# OPA567.net
KiCad netlist of a schematic drawn in Altium Designer
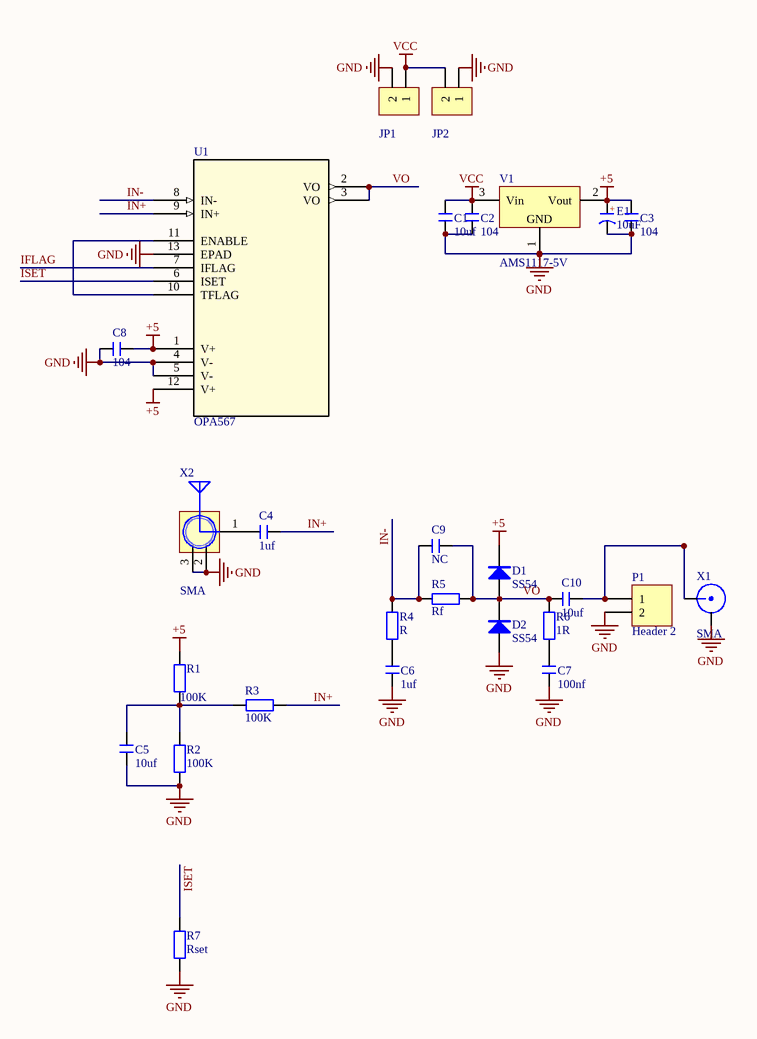
[diagram p0: OPA567.SchDoc]

(export (version "E")
  (design (tool "Eeschema 10.0.6"))
  (components
    (comp (ref "C1")
      (value "10uf")
      (footprint "C 0603_L")
      (description "无极性贴片电容")
      (fields (field (name "版权归属") "源创客"))
      (libsource (lib "IL") (part "C"))
    )
    (comp (ref "C2")
      (value "104")
      (footprint "C 0603_L")
      (description "无极性贴片电容")
      (fields (field (name "版权归属") "源创客"))
      (libsource (lib "IL") (part "C"))
    )
    (comp (ref "C3")
      (value "104")
      (footprint "C 0603_L")
      (description "无极性贴片电容")
      (fields (field (name "版权归属") "源创客"))
      (libsource (lib "IL") (part "C"))
    )
    (comp (ref "C4")
      (value "1uf")
      (footprint "C 0603_L")
      (description "无极性贴片电容")
      (fields (field (name "版权归属") "源创客"))
      (libsource (lib "IL") (part "C"))
    )
    (comp (ref "C5")
      (value "10uf")
      (footprint "C 0603_L")
      (description "无极性贴片电容")
      (fields (field (name "版权归属") "源创客"))
      (libsource (lib "IL") (part "C"))
    )
    (comp (ref "C6")
      (value "1uf")
      (footprint "C 0603_L")
      (description "无极性贴片电容")
      (fields (field (name "版权归属") "源创客"))
      (libsource (lib "IL") (part "C"))
    )
    (comp (ref "C7")
      (value "100nf")
      (footprint "C 0603_L")
      (description "无极性贴片电容")
      (fields (field (name "版权归属") "源创客"))
      (libsource (lib "IL") (part "C"))
    )
    (comp (ref "C8")
      (value "104")
      (footprint "C 0603_L")
      (description "无极性贴片电容")
      (fields (field (name "版权归属") "源创客"))
      (libsource (lib "IL") (part "C"))
    )
    (comp (ref "C9")
      (value "NC")
      (footprint "C 0603_L")
      (description "无极性贴片电容")
      (fields (field (name "版权归属") "源创客"))
      (libsource (lib "IL") (part "C"))
    )
    (comp (ref "C10")
      (value "10uf")
      (footprint "C 0603_L")
      (description "无极性贴片电容")
      (fields (field (name "版权归属") "源创客"))
      (libsource (lib "IL") (part "C"))
    )
    (comp (ref "D1")
      (value "SS54")
      (footprint "SMA")
      (description "肖特基二极管")
      (fields (field (name "版权归属") "源创客"))
      (libsource (lib "IL") (part "SR540"))
    )
    (comp (ref "D2")
      (value "SS54")
      (footprint "SMA")
      (description "肖特基二极管")
      (fields (field (name "版权归属") "源创客"))
      (libsource (lib "IL") (part "SR540"))
    )
    (comp (ref "E1")
      (value "10uF")
      (footprint "CD B(3528)")
      (description "贴片钽电容")
      (fields (field (name "版权归属") "源创客"))
      (libsource (lib "IL") (part "C-CD"))
    )
    (comp (ref "JP1")
      (value "HDR-1X2")
      (footprint "VH3.96-LI-2P")
      (description "2P接插件")
      (fields (field (name "版权归属") "源创客"))
      (libsource (lib "IL") (part "Header 2_1"))
    )
    (comp (ref "JP2")
      (value "HDR-1X2")
      (footprint "VH3.96-LI-2P")
      (description "2P接插件")
      (fields (field (name "版权归属") "源创客"))
      (libsource (lib "IL") (part "Header 2_1"))
    )
    (comp (ref "P1")
      (value "Header 2")
      (footprint "HDR1X2")
      (description "Header, 2-Pin")
      (fields (field (name "PUBLISHER") "Altium Limited"))
      (libsource (lib "Miscellaneous Connectors") (part "Header 2"))
    )
    (comp (ref "R1")
      (value "100K")
      (footprint "R 0603_L")
      (description "贴片电阻")
      (fields (field (name "版权归属") "源创客"))
      (libsource (lib "IL") (part "R"))
    )
    (comp (ref "R2")
      (value "100K")
      (footprint "R 0603_L")
      (description "贴片电阻")
      (fields (field (name "版权归属") "源创客"))
      (libsource (lib "IL") (part "R"))
    )
    (comp (ref "R3")
      (value "100K")
      (footprint "R 0603_L")
      (description "贴片电阻")
      (fields (field (name "版权归属") "源创客"))
      (libsource (lib "IL") (part "R"))
    )
    (comp (ref "R4")
      (value "R")
      (footprint "R 0603_L")
      (description "贴片电阻")
      (fields (field (name "版权归属") "源创客"))
      (libsource (lib "IL") (part "R"))
    )
    (comp (ref "R5")
      (value "Rf")
      (footprint "R 0603_L")
      (description "贴片电阻")
      (fields (field (name "版权归属") "源创客"))
      (libsource (lib "IL") (part "R"))
    )
    (comp (ref "R6")
      (value "1R")
      (footprint "R 0603_L")
      (description "贴片电阻")
      (fields (field (name "版权归属") "源创客"))
      (libsource (lib "IL") (part "R"))
    )
    (comp (ref "R7")
      (value "Rset")
      (footprint "R 0603_L")
      (description "贴片电阻")
      (fields (field (name "版权归属") "源创客"))
      (libsource (lib "IL") (part "R"))
    )
    (comp (ref "U1")
      (value "OPA567")
      (footprint "RHG12_3P12X3P12")
      (description "2A,5V功率放大器")
      (fields
        (field (name "MANUFACTURER_PART_NUMBER") "OPA567AIRHGR")
        (field (name "COPYRIGHT") "Copyright (C) 2021 Ultra Librarian. All rights reserved.")
      )
      (libsource (lib "IL") (part "OPA567AIRHGR"))
    )
    (comp (ref "V1")
      (value "AMS1117-5V")
      (footprint "SOT223_L")
      (description "三端稳压芯片")
      (fields (field (name "版权归属") "源创客"))
      (libsource (lib "IL") (part "AMS1117"))
    )
    (comp (ref "X1") (value "SMA") (footprint "SMA1") (libsource (lib "Library") (part "SMA")))
    (comp (ref "X2")
      (value "SMA")
      (footprint "SMA-KE")
      (description "SMA-2.4G射频天线接口")
      (fields (field (name "版权归属") "源创客"))
      (libsource (lib "IL") (part "SMA"))
    )
  )
  (nets
    (net (code "1") (name "+5") (class "Default")
      (node (ref "C3") (pin "2") (pinfunction "2_2") (pintype "passive"))
      (node (ref "C8") (pin "1") (pinfunction "1_1") (pintype "passive"))
      (node (ref "D1") (pin "2") (pinfunction "K_2") (pintype "passive"))
      (node (ref "E1") (pin "1") (pinfunction "A_1") (pintype "passive"))
      (node (ref "R1") (pin "2") (pinfunction "2_2") (pintype "passive"))
      (node (ref "U1") (pin "1") (pinfunction "V+_1") (pintype "power_in"))
      (node (ref "U1") (pin "12") (pinfunction "V+_12") (pintype "power_in"))
      (node (ref "V1") (pin "2") (pinfunction "Vout_2") (pintype "passive"))
    )
    (net (code "2") (name "/IFLAG") (class "Default")
      (node (ref "U1") (pin "7") (pinfunction "IFLAG_7") (pintype "passive"))
    )
    (net (code "3") (name "/IN+") (class "Default")
      (node (ref "C4") (pin "1") (pinfunction "1_1") (pintype "passive"))
      (node (ref "R3") (pin "2") (pinfunction "2_2") (pintype "passive"))
      (node (ref "U1") (pin "9") (pinfunction "IN+_9") (pintype "input"))
    )
    (net (code "4") (name "/IN-") (class "Default")
      (node (ref "C9") (pin "2") (pinfunction "2_2") (pintype "passive"))
      (node (ref "R4") (pin "2") (pinfunction "2_2") (pintype "passive"))
      (node (ref "R5") (pin "2") (pinfunction "2_2") (pintype "passive"))
      (node (ref "U1") (pin "8") (pinfunction "IN-_8") (pintype "input"))
    )
    (net (code "5") (name "/ISET") (class "Default")
      (node (ref "R7") (pin "1") (pinfunction "1_1") (pintype "passive"))
      (node (ref "U1") (pin "6") (pinfunction "ISET_6") (pintype "passive"))
    )
    (net (code "6") (name "/VO") (class "Default")
      (node (ref "C10") (pin "2") (pinfunction "2_2") (pintype "passive"))
      (node (ref "C9") (pin "1") (pinfunction "1_1") (pintype "passive"))
      (node (ref "D1") (pin "1") (pinfunction "A_1") (pintype "passive"))
      (node (ref "D2") (pin "2") (pinfunction "K_2") (pintype "passive"))
      (node (ref "R5") (pin "1") (pinfunction "1_1") (pintype "passive"))
      (node (ref "R6") (pin "2") (pinfunction "2_2") (pintype "passive"))
      (node (ref "U1") (pin "2") (pinfunction "VO_2") (pintype "output"))
      (node (ref "U1") (pin "3") (pinfunction "VO_3") (pintype "output"))
    )
    (net (code "7") (name "GND") (class "Default")
      (node (ref "C1") (pin "1") (pinfunction "1_1") (pintype "passive"))
      (node (ref "C2") (pin "1") (pinfunction "1_1") (pintype "passive"))
      (node (ref "C3") (pin "1") (pinfunction "1_1") (pintype "passive"))
      (node (ref "C5") (pin "2") (pinfunction "2_2") (pintype "passive"))
      (node (ref "C6") (pin "1") (pinfunction "1_1") (pintype "passive"))
      (node (ref "C7") (pin "1") (pinfunction "1_1") (pintype "passive"))
      (node (ref "C8") (pin "2") (pinfunction "2_2") (pintype "passive"))
      (node (ref "D2") (pin "1") (pinfunction "A_1") (pintype "passive"))
      (node (ref "E1") (pin "2") (pinfunction "K_2") (pintype "passive"))
      (node (ref "JP1") (pin "2") (pinfunction "2_2") (pintype "passive"))
      (node (ref "JP2") (pin "1") (pinfunction "1_1") (pintype "passive"))
      (node (ref "P1") (pin "2") (pinfunction "2_2") (pintype "passive"))
      (node (ref "R2") (pin "1") (pinfunction "1_1") (pintype "passive"))
      (node (ref "R7") (pin "2") (pinfunction "2_2") (pintype "passive"))
      (node (ref "U1") (pin "13") (pinfunction "EPAD_13") (pintype "passive"))
      (node (ref "U1") (pin "4") (pinfunction "V-_4") (pintype "power_in"))
      (node (ref "U1") (pin "5") (pinfunction "V-_5") (pintype "power_in"))
      (node (ref "V1") (pin "1") (pinfunction "GND_1") (pintype "passive"))
      (node (ref "X1") (pin "2") (pinfunction "2_2") (pintype "passive"))
      (node (ref "X2") (pin "2") (pinfunction "GND_2") (pintype "passive"))
      (node (ref "X2") (pin "3") (pinfunction "GND_3") (pintype "passive"))
    )
    (net (code "8") (name "Net-(C5-Pad1)") (class "Default")
      (node (ref "C5") (pin "1") (pinfunction "1_1") (pintype "passive"))
      (node (ref "R1") (pin "1") (pinfunction "1_1") (pintype "passive"))
      (node (ref "R2") (pin "2") (pinfunction "2_2") (pintype "passive"))
      (node (ref "R3") (pin "1") (pinfunction "1_1") (pintype "passive"))
    )
    (net (code "9") (name "Net-(C6-Pad2)") (class "Default")
      (node (ref "C6") (pin "2") (pinfunction "2_2") (pintype "passive"))
      (node (ref "R4") (pin "1") (pinfunction "1_1") (pintype "passive"))
    )
    (net (code "10") (name "Net-(C7-Pad2)") (class "Default")
      (node (ref "C7") (pin "2") (pinfunction "2_2") (pintype "passive"))
      (node (ref "R6") (pin "1") (pinfunction "1_1") (pintype "passive"))
    )
    (net (code "11") (name "Net-(C10-Pad1)") (class "Default")
      (node (ref "C10") (pin "1") (pinfunction "1_1") (pintype "passive"))
      (node (ref "P1") (pin "1") (pinfunction "1_1") (pintype "passive"))
      (node (ref "X1") (pin "1") (pinfunction "1_1") (pintype "passive"))
    )
    (net (code "12") (name "Net-(U1-ENABLE)") (class "Default")
      (node (ref "U1") (pin "10") (pinfunction "TFLAG_10") (pintype "passive"))
      (node (ref "U1") (pin "11") (pinfunction "ENABLE_11") (pintype "passive"))
    )
    (net (code "13") (name "Net-(X2-ANT)") (class "Default")
      (node (ref "C4") (pin "2") (pinfunction "2_2") (pintype "passive"))
      (node (ref "X2") (pin "1") (pinfunction "ANT_1") (pintype "passive"))
    )
    (net (code "14") (name "VCC") (class "Default")
      (node (ref "C1") (pin "2") (pinfunction "2_2") (pintype "passive"))
      (node (ref "C2") (pin "2") (pinfunction "2_2") (pintype "passive"))
      (node (ref "JP1") (pin "1") (pinfunction "1_1") (pintype "passive"))
      (node (ref "JP2") (pin "2") (pinfunction "2_2") (pintype "passive"))
      (node (ref "V1") (pin "3") (pinfunction "Vin_3") (pintype "passive"))
    )
  )
)
